# perf_board.net
KiCad netlist of a schematic drawn in EAGLE
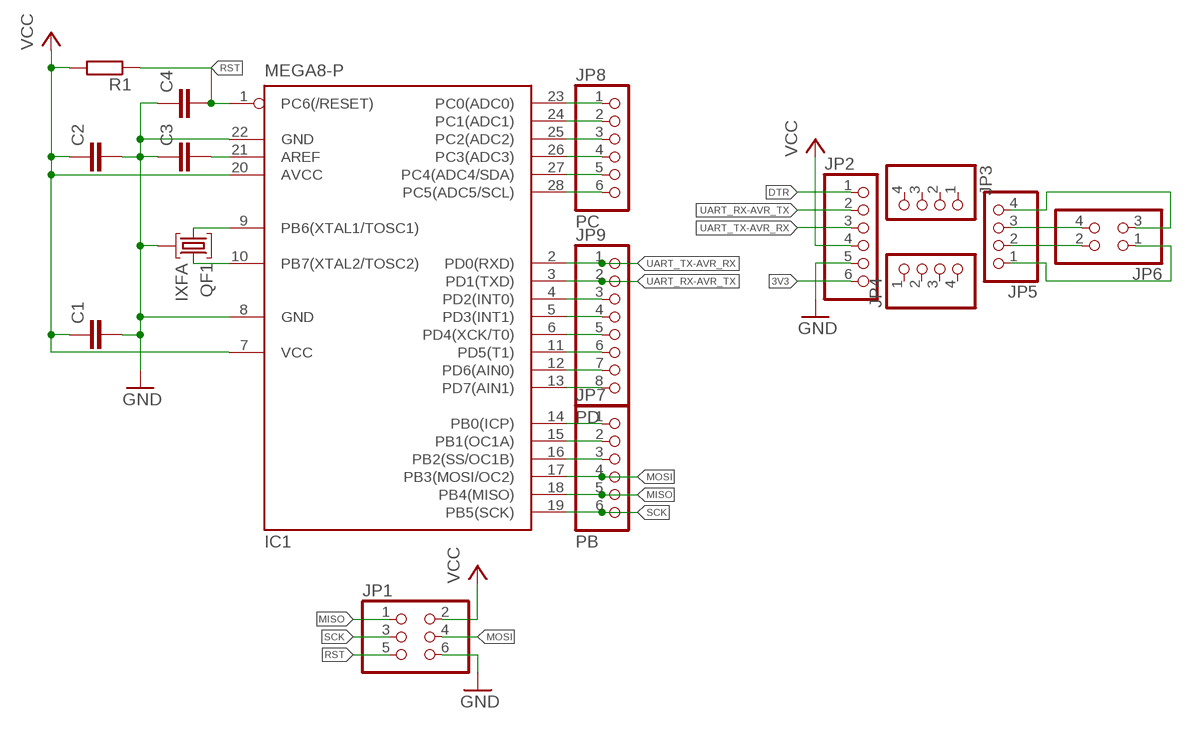
[diagram p0: schematic, sheet 1]

(export (version "E")
  (design (tool "Eeschema 10.0.6"))
  (components
    (comp (ref "C1")
      (value "C-EUC0603")
      (footprint "eagle-import:C0603")
      (libsource (lib "eagle-import") (part "C-EUC0603"))
    )
    (comp (ref "C2")
      (value "C-EUC0603")
      (footprint "eagle-import:C0603")
      (libsource (lib "eagle-import") (part "C-EUC0603"))
    )
    (comp (ref "C3")
      (value "C-EUC0603")
      (footprint "eagle-import:C0603")
      (libsource (lib "eagle-import") (part "C-EUC0603"))
    )
    (comp (ref "C4")
      (value "C-EUC0603")
      (footprint "eagle-import:C0603")
      (libsource (lib "eagle-import") (part "C-EUC0603"))
    )
    (comp (ref "IC1")
      (value "MEGA8-P")
      (footprint "eagle-import:DIL28-3")
      (libsource (lib "eagle-import") (part "MEGA8-P"))
    )
    (comp (ref "JP1")
      (value "PINHD-2X3")
      (footprint "eagle-import:2X03")
      (libsource (lib "eagle-import") (part "PINHD-2X3"))
    )
    (comp (ref "JP2")
      (value "PINHD-1X6")
      (footprint "eagle-import:1X06")
      (libsource (lib "eagle-import") (part "PINHD-1X6"))
    )
    (comp (ref "JP3")
      (value "PINHD-1X4")
      (footprint "eagle-import:1X04")
      (libsource (lib "eagle-import") (part "PINHD-1X4"))
    )
    (comp (ref "JP4")
      (value "PINHD-1X4")
      (footprint "eagle-import:1X04")
      (libsource (lib "eagle-import") (part "PINHD-1X4"))
    )
    (comp (ref "JP5")
      (value "PINHD-1X4")
      (footprint "eagle-import:1X04")
      (libsource (lib "eagle-import") (part "PINHD-1X4"))
    )
    (comp (ref "JP6")
      (value "PINHD-2X2")
      (footprint "eagle-import:2X02")
      (libsource (lib "eagle-import") (part "PINHD-2X2"))
    )
    (comp (ref "JP7")
      (value "PB")
      (footprint "eagle-import:1X06")
      (libsource (lib "eagle-import") (part "PINHD-1X6"))
    )
    (comp (ref "JP8")
      (value "PC")
      (footprint "eagle-import:1X06")
      (libsource (lib "eagle-import") (part "PINHD-1X6"))
    )
    (comp (ref "JP9")
      (value "PD")
      (footprint "eagle-import:1X08")
      (libsource (lib "eagle-import") (part "PINHD-1X8"))
    )
    (comp (ref "QF1")
      (value "IXFA")
      (footprint "eagle-import:HC49U")
      (libsource (lib "eagle-import") (part "IXFA"))
    )
    (comp (ref "R1")
      (value "R-EU_R0603")
      (footprint "eagle-import:R0603")
      (libsource (lib "eagle-import") (part "R-EU_R0603"))
    )
  )
  (nets
    (net (code "1") (name "3V3") (class "Default")
      (node (ref "JP2") (pin "6") (pinfunction "6_6") (pintype "passive"))
    )
    (net (code "2") (name "DTR") (class "Default")
      (node (ref "JP2") (pin "1") (pinfunction "1_1") (pintype "passive"))
    )
    (net (code "3") (name "GND") (class "Default")
      (node (ref "C1") (pin "2") (pinfunction "2_2") (pintype "passive"))
      (node (ref "C2") (pin "2") (pinfunction "2_2") (pintype "passive"))
      (node (ref "C3") (pin "1") (pinfunction "1_1") (pintype "passive"))
      (node (ref "C4") (pin "1") (pinfunction "1_1") (pintype "passive"))
      (node (ref "IC1") (pin "22") (pinfunction "GND_22") (pintype "power_in"))
      (node (ref "IC1") (pin "8") (pinfunction "GND_8") (pintype "power_in"))
      (node (ref "JP1") (pin "6") (pinfunction "6_6") (pintype "passive"))
      (node (ref "JP2") (pin "5") (pinfunction "5_5") (pintype "passive"))
      (node (ref "QF1") (pin "2") (pinfunction "2_2") (pintype "passive"))
    )
    (net (code "4") (name "MISO") (class "Default")
      (node (ref "IC1") (pin "18") (pinfunction "PB4(MISO)_18") (pintype "bidirectional"))
      (node (ref "JP1") (pin "1") (pinfunction "1_1") (pintype "passive"))
      (node (ref "JP7") (pin "5") (pinfunction "5_5") (pintype "passive"))
    )
    (net (code "5") (name "MOSI") (class "Default")
      (node (ref "IC1") (pin "17") (pinfunction "PB3(MOSI/OC2)_17") (pintype "bidirectional"))
      (node (ref "JP1") (pin "4") (pinfunction "4_4") (pintype "passive"))
      (node (ref "JP7") (pin "4") (pinfunction "4_4") (pintype "passive"))
    )
    (net (code "6") (name "Net-(IC1-AREF)") (class "Default")
      (node (ref "C3") (pin "2") (pinfunction "2_2") (pintype "passive"))
      (node (ref "IC1") (pin "21") (pinfunction "AREF_21") (pintype "passive"))
    )
    (net (code "7") (name "Net-(IC1-PB0(ICP))") (class "Default")
      (node (ref "IC1") (pin "14") (pinfunction "PB0(ICP)_14") (pintype "bidirectional"))
      (node (ref "JP7") (pin "1") (pinfunction "1_1") (pintype "passive"))
    )
    (net (code "8") (name "Net-(IC1-PB1(OC1A))") (class "Default")
      (node (ref "IC1") (pin "15") (pinfunction "PB1(OC1A)_15") (pintype "bidirectional"))
      (node (ref "JP7") (pin "2") (pinfunction "2_2") (pintype "passive"))
    )
    (net (code "9") (name "Net-(IC1-PB2(SS{slash}OC1B))") (class "Default")
      (node (ref "IC1") (pin "16") (pinfunction "PB2(SS/OC1B)_16") (pintype "bidirectional"))
      (node (ref "JP7") (pin "3") (pinfunction "3_3") (pintype "passive"))
    )
    (net (code "10") (name "Net-(IC1-PB6(XTAL1{slash}TOSC1))") (class "Default")
      (node (ref "IC1") (pin "9") (pinfunction "PB6(XTAL1/TOSC1)_9") (pintype "bidirectional"))
      (node (ref "QF1") (pin "1") (pinfunction "1_1") (pintype "passive"))
    )
    (net (code "11") (name "Net-(IC1-PB7(XTAL2{slash}TOSC2))") (class "Default")
      (node (ref "IC1") (pin "10") (pinfunction "PB7(XTAL2/TOSC2)_10") (pintype "bidirectional"))
      (node (ref "QF1") (pin "3") (pinfunction "3_3") (pintype "passive"))
    )
    (net (code "12") (name "Net-(IC1-PC0(ADC0))") (class "Default")
      (node (ref "IC1") (pin "23") (pinfunction "PC0(ADC0)_23") (pintype "bidirectional"))
      (node (ref "JP8") (pin "1") (pinfunction "1_1") (pintype "passive"))
    )
    (net (code "13") (name "Net-(IC1-PC1(ADC1))") (class "Default")
      (node (ref "IC1") (pin "24") (pinfunction "PC1(ADC1)_24") (pintype "bidirectional"))
      (node (ref "JP8") (pin "2") (pinfunction "2_2") (pintype "passive"))
    )
    (net (code "14") (name "Net-(IC1-PC2(ADC2))") (class "Default")
      (node (ref "IC1") (pin "25") (pinfunction "PC2(ADC2)_25") (pintype "bidirectional"))
      (node (ref "JP8") (pin "3") (pinfunction "3_3") (pintype "passive"))
    )
    (net (code "15") (name "Net-(IC1-PC3(ADC3))") (class "Default")
      (node (ref "IC1") (pin "26") (pinfunction "PC3(ADC3)_26") (pintype "bidirectional"))
      (node (ref "JP8") (pin "4") (pinfunction "4_4") (pintype "passive"))
    )
    (net (code "16") (name "Net-(IC1-PC4(ADC4{slash}SDA))") (class "Default")
      (node (ref "IC1") (pin "27") (pinfunction "PC4(ADC4/SDA)_27") (pintype "bidirectional"))
      (node (ref "JP8") (pin "5") (pinfunction "5_5") (pintype "passive"))
    )
    (net (code "17") (name "Net-(IC1-PC5(ADC5{slash}SCL))") (class "Default")
      (node (ref "IC1") (pin "28") (pinfunction "PC5(ADC5/SCL)_28") (pintype "bidirectional"))
      (node (ref "JP8") (pin "6") (pinfunction "6_6") (pintype "passive"))
    )
    (net (code "18") (name "Net-(IC1-PD2(INT0))") (class "Default")
      (node (ref "IC1") (pin "4") (pinfunction "PD2(INT0)_4") (pintype "bidirectional"))
      (node (ref "JP9") (pin "3") (pinfunction "3_3") (pintype "passive"))
    )
    (net (code "19") (name "Net-(IC1-PD3(INT1))") (class "Default")
      (node (ref "IC1") (pin "5") (pinfunction "PD3(INT1)_5") (pintype "bidirectional"))
      (node (ref "JP9") (pin "4") (pinfunction "4_4") (pintype "passive"))
    )
    (net (code "20") (name "Net-(IC1-PD4(XCK{slash}T0))") (class "Default")
      (node (ref "IC1") (pin "6") (pinfunction "PD4(XCK/T0)_6") (pintype "bidirectional"))
      (node (ref "JP9") (pin "5") (pinfunction "5_5") (pintype "passive"))
    )
    (net (code "21") (name "Net-(IC1-PD5(T1))") (class "Default")
      (node (ref "IC1") (pin "11") (pinfunction "PD5(T1)_11") (pintype "bidirectional"))
      (node (ref "JP9") (pin "6") (pinfunction "6_6") (pintype "passive"))
    )
    (net (code "22") (name "Net-(IC1-PD6(AIN0))") (class "Default")
      (node (ref "IC1") (pin "12") (pinfunction "PD6(AIN0)_12") (pintype "bidirectional"))
      (node (ref "JP9") (pin "7") (pinfunction "7_7") (pintype "passive"))
    )
    (net (code "23") (name "Net-(IC1-PD7(AIN1))") (class "Default")
      (node (ref "IC1") (pin "13") (pinfunction "PD7(AIN1)_13") (pintype "bidirectional"))
      (node (ref "JP9") (pin "8") (pinfunction "8_8") (pintype "passive"))
    )
    (net (code "24") (name "Net-(JP5-Pad1)") (class "Default")
      (node (ref "JP5") (pin "1") (pinfunction "1_1") (pintype "passive"))
      (node (ref "JP6") (pin "1") (pinfunction "1_1") (pintype "passive"))
    )
    (net (code "25") (name "Net-(JP5-Pad2)") (class "Default")
      (node (ref "JP5") (pin "2") (pinfunction "2_2") (pintype "passive"))
      (node (ref "JP6") (pin "2") (pinfunction "2_2") (pintype "passive"))
    )
    (net (code "26") (name "Net-(JP5-Pad3)") (class "Default")
      (node (ref "JP5") (pin "3") (pinfunction "3_3") (pintype "passive"))
      (node (ref "JP6") (pin "4") (pinfunction "4_4") (pintype "passive"))
    )
    (net (code "27") (name "Net-(JP5-Pad4)") (class "Default")
      (node (ref "JP5") (pin "4") (pinfunction "4_4") (pintype "passive"))
      (node (ref "JP6") (pin "3") (pinfunction "3_3") (pintype "passive"))
    )
    (net (code "28") (name "RST") (class "Default")
      (node (ref "C4") (pin "2") (pinfunction "2_2") (pintype "passive"))
      (node (ref "IC1") (pin "1") (pinfunction "PC6(/RESET)_1") (pintype "bidirectional"))
      (node (ref "JP1") (pin "5") (pinfunction "5_5") (pintype "passive"))
      (node (ref "R1") (pin "1") (pinfunction "1_1") (pintype "passive"))
    )
    (net (code "29") (name "SCK") (class "Default")
      (node (ref "IC1") (pin "19") (pinfunction "PB5(SCK)_19") (pintype "bidirectional"))
      (node (ref "JP1") (pin "3") (pinfunction "3_3") (pintype "passive"))
      (node (ref "JP7") (pin "6") (pinfunction "6_6") (pintype "passive"))
    )
    (net (code "30") (name "UART_RX-AVR_TX") (class "Default")
      (node (ref "IC1") (pin "3") (pinfunction "PD1(TXD)_3") (pintype "bidirectional"))
      (node (ref "JP2") (pin "2") (pinfunction "2_2") (pintype "passive"))
      (node (ref "JP9") (pin "2") (pinfunction "2_2") (pintype "passive"))
    )
    (net (code "31") (name "UART_TX-AVR_RX") (class "Default")
      (node (ref "IC1") (pin "2") (pinfunction "PD0(RXD)_2") (pintype "bidirectional"))
      (node (ref "JP2") (pin "3") (pinfunction "3_3") (pintype "passive"))
      (node (ref "JP9") (pin "1") (pinfunction "1_1") (pintype "passive"))
    )
    (net (code "32") (name "VCC") (class "Default")
      (node (ref "C1") (pin "1") (pinfunction "1_1") (pintype "passive"))
      (node (ref "C2") (pin "1") (pinfunction "1_1") (pintype "passive"))
      (node (ref "IC1") (pin "20") (pinfunction "AVCC_20") (pintype "power_in"))
      (node (ref "IC1") (pin "7") (pinfunction "VCC_7") (pintype "power_in"))
      (node (ref "JP1") (pin "2") (pinfunction "2_2") (pintype "passive"))
      (node (ref "JP2") (pin "4") (pinfunction "4_4") (pintype "passive"))
      (node (ref "R1") (pin "2") (pinfunction "2_2") (pintype "passive"))
    )
    (net (code "33") (name "unconnected-(JP3-Pad1)") (class "Default")
      (node (ref "JP3") (pin "1") (pinfunction "1_1") (pintype "passive"))
    )
    (net (code "34") (name "unconnected-(JP3-Pad2)") (class "Default")
      (node (ref "JP3") (pin "2") (pinfunction "2_2") (pintype "passive"))
    )
    (net (code "35") (name "unconnected-(JP3-Pad3)") (class "Default")
      (node (ref "JP3") (pin "3") (pinfunction "3_3") (pintype "passive"))
    )
    (net (code "36") (name "unconnected-(JP3-Pad4)") (class "Default")
      (node (ref "JP3") (pin "4") (pinfunction "4_4") (pintype "passive"))
    )
    (net (code "37") (name "unconnected-(JP4-Pad1)") (class "Default")
      (node (ref "JP4") (pin "1") (pinfunction "1_1") (pintype "passive"))
    )
    (net (code "38") (name "unconnected-(JP4-Pad2)") (class "Default")
      (node (ref "JP4") (pin "2") (pinfunction "2_2") (pintype "passive"))
    )
    (net (code "39") (name "unconnected-(JP4-Pad3)") (class "Default")
      (node (ref "JP4") (pin "3") (pinfunction "3_3") (pintype "passive"))
    )
    (net (code "40") (name "unconnected-(JP4-Pad4)") (class "Default")
      (node (ref "JP4") (pin "4") (pinfunction "4_4") (pintype "passive"))
    )
  )
)
